# Sheet_MP3Player_DAC__V3_0.net
KiCad netlist of a schematic drawn in Altium Designer
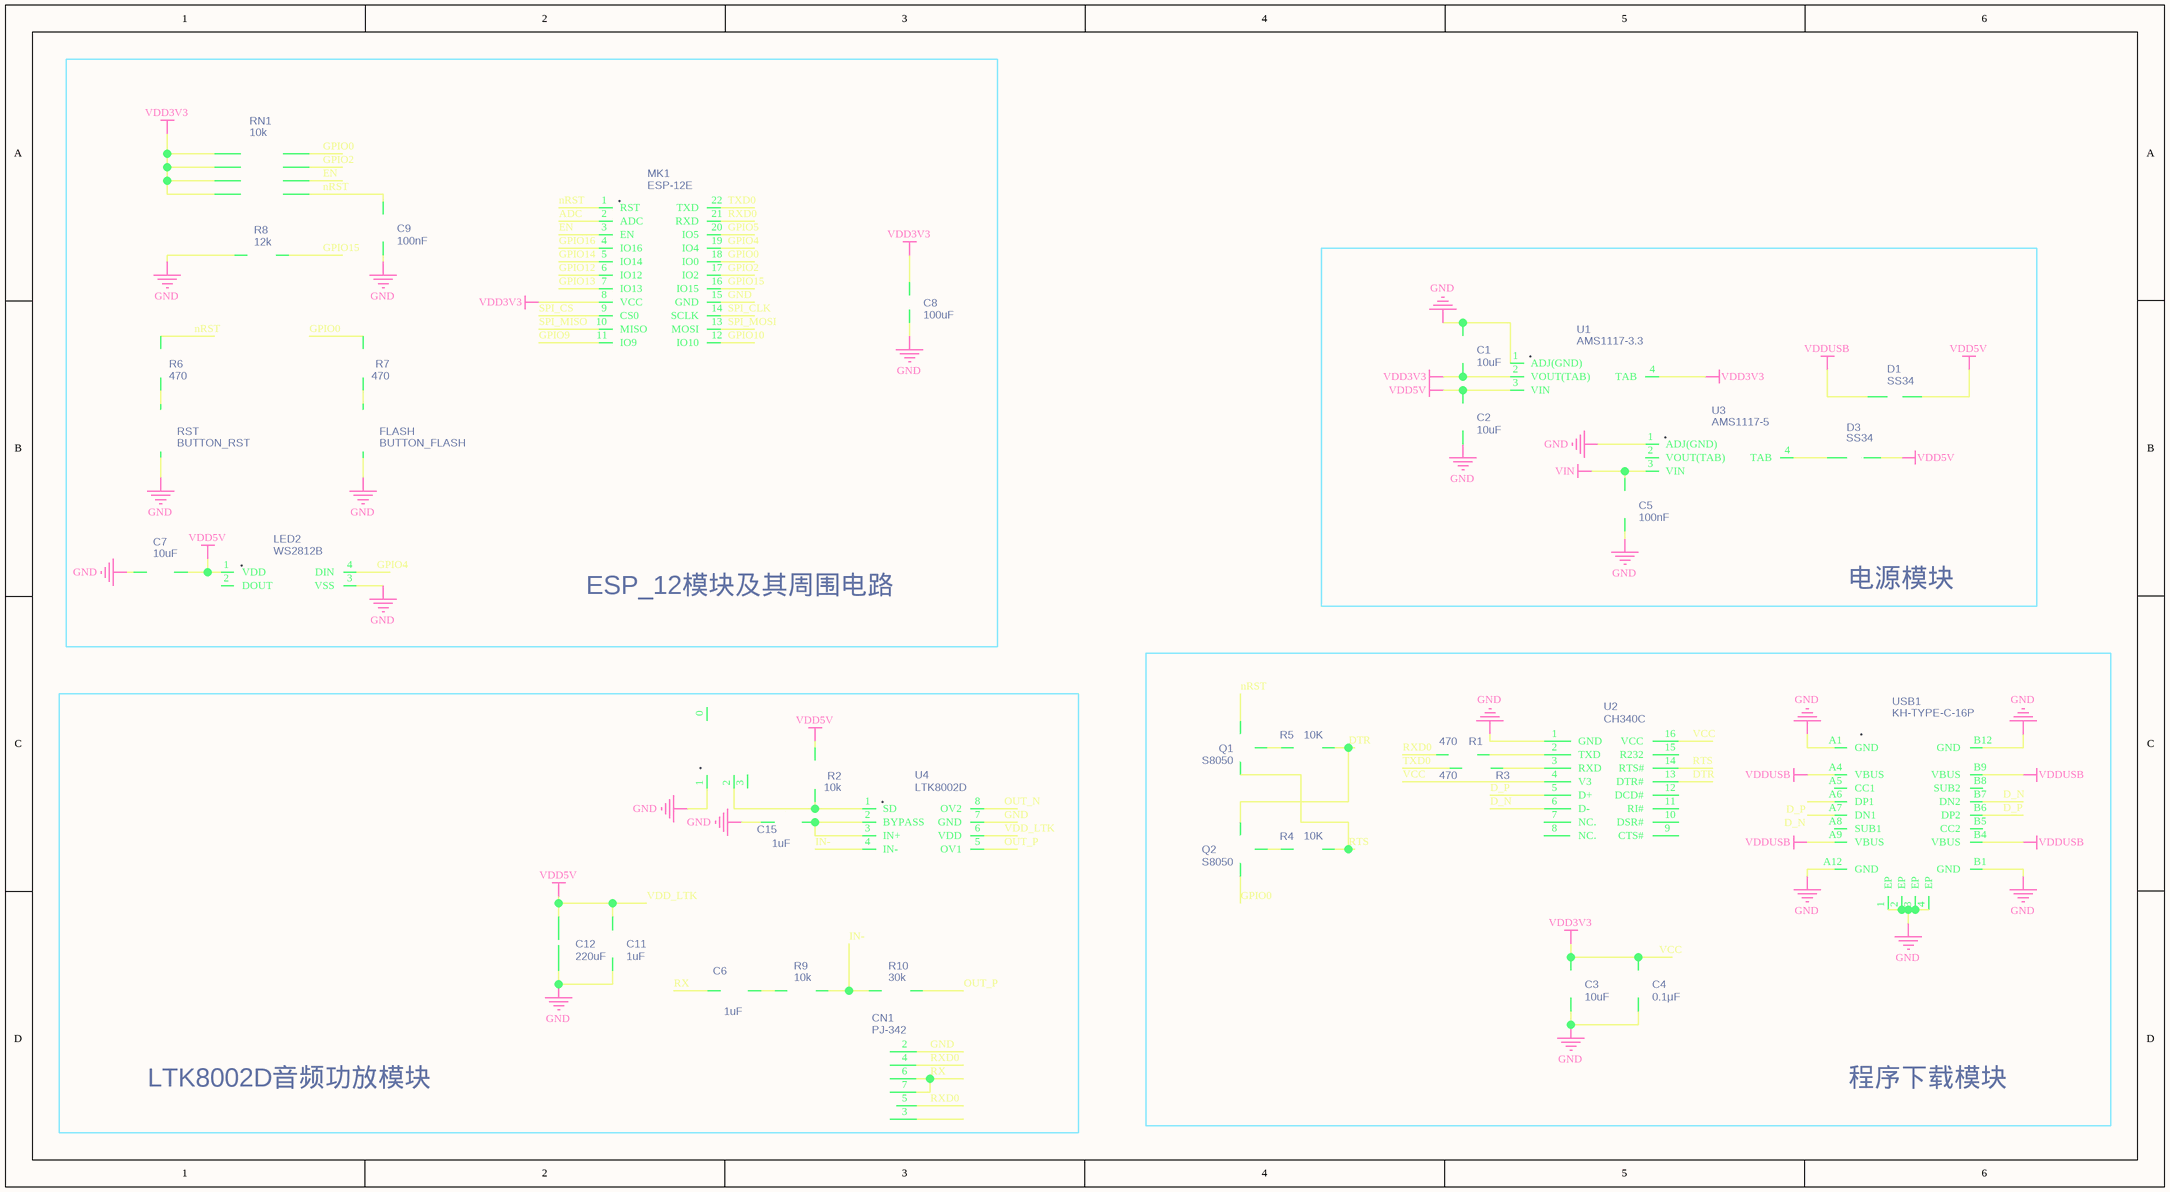
[diagram p0: Sheet_MP3Player(DAC)_V3.0.schdoc]

(export (version "E")
  (design (tool "Eeschema 10.0.6"))
  (components
    (comp (ref "C1")
      (value "10uF")
      (fields
        (field (name "BOM_SUPPLIER PART") "C338150")
        (field (name "BOM_MANUFACTURER PART") "0603B101K500CT")
        (field (name "CONTRIBUTOR") "LCSC")
      )
      (libsource (lib "altium-import") (part "root_1_10uF_"))
    )
    (comp (ref "C2")
      (value "10uF")
      (fields
        (field (name "BOM_SUPPLIER PART") "C338150")
        (field (name "BOM_MANUFACTURER PART") "0603B101K500CT")
        (field (name "CONTRIBUTOR") "LCSC")
      )
      (libsource (lib "altium-import") (part "root_1_10uF_"))
    )
    (comp (ref "C3")
      (value "10uF")
      (fields
        (field (name "BOM_SUPPLIER PART") "C338150")
        (field (name "BOM_MANUFACTURER PART") "0603B101K500CT")
        (field (name "CONTRIBUTOR") "LCSC")
      )
      (libsource (lib "altium-import") (part "root_1_10uF_"))
    )
    (comp (ref "C4")
      (value "0.1μF")
      (fields
        (field (name "BOM_SUPPLIER PART") "C338150")
        (field (name "BOM_MANUFACTURER PART") "0603B101K500CT")
        (field (name "CONTRIBUTOR") "LCSC")
      )
      (libsource (lib "altium-import") (part "root_1_0.1μF_"))
    )
    (comp (ref "C5")
      (value "100nF")
      (fields
        (field (name "BOM_SUPPLIER PART") "C338150")
        (field (name "BOM_MANUFACTURER PART") "0603B101K500CT")
        (field (name "CONTRIBUTOR") "LCSC")
      )
      (libsource (lib "altium-import") (part "root_1_100nF_"))
    )
    (comp (ref "C6")
      (value "1uF")
      (fields
        (field (name "BOM_SUPPLIER PART") "C338150")
        (field (name "BOM_MANUFACTURER PART") "0603B101K500CT")
        (field (name "CONTRIBUTOR") "LCSC")
      )
      (libsource (lib "altium-import") (part "root_0_1uF_"))
    )
    (comp (ref "C7")
      (value "10uF")
      (fields
        (field (name "BOM_SUPPLIER PART") "C338150")
        (field (name "BOM_MANUFACTURER PART") "0603B101K500CT")
        (field (name "CONTRIBUTOR") "LCSC")
      )
      (libsource (lib "altium-import") (part "root_2_10uF_"))
    )
    (comp (ref "C8")
      (value "100uF")
      (fields
        (field (name "BOM_MANUFACTURER PART") "TAJB107M006RNJ")
        (field (name "BOM_SUPPLIER PART") "C7195")
      )
      (libsource (lib "altium-import") (part "root_1_100uF_"))
    )
    (comp (ref "C9")
      (value "100nF")
      (fields
        (field (name "BOM_SUPPLIER PART") "C338150")
        (field (name "BOM_MANUFACTURER PART") "0603B101K500CT")
        (field (name "CONTRIBUTOR") "LCSC")
      )
      (libsource (lib "altium-import") (part "root_1_100nF_"))
    )
    (comp (ref "C11")
      (value "1uF")
      (fields
        (field (name "BOM_SUPPLIER PART") "C338150")
        (field (name "BOM_MANUFACTURER PART") "0603B101K500CT")
        (field (name "CONTRIBUTOR") "LCSC")
      )
      (libsource (lib "altium-import") (part "root_3_1uF_"))
    )
    (comp (ref "C12")
      (value "220uF")
      (fields
        (field (name "BOM_SUPPLIER PART") "C371974")
        (field (name "BOM_MANUFACTURER PART") "VZT221M1ETR-0607")
        (field (name "CONTRIBUTOR") "LCSC")
      )
      (libsource (lib "altium-import") (part "root_0_220uF_"))
    )
    (comp (ref "C15")
      (value "1uF")
      (fields
        (field (name "BOM_SUPPLIER PART") "C338150")
        (field (name "BOM_MANUFACTURER PART") "0603B101K500CT")
        (field (name "CONTRIBUTOR") "LCSC")
      )
      (libsource (lib "altium-import") (part "root_0_1uF_"))
    )
    (comp (ref "CN1")
      (value "PJ-342")
      (fields (field (name "BOM_SUPPLIER PART") "C668606") (field (name "CONTRIBUTOR") "LCSC"))
      (libsource (lib "altium-import") (part "root_0_PJ-342_"))
    )
    (comp (ref "D1")
      (value "SS34")
      (fields (field (name "BOM_SUPPLIER PART") "C83961"))
      (libsource (lib "") (part "root_2_SS34__1"))
    )
    (comp (ref "D3")
      (value "SS34")
      (fields (field (name "BOM_MANUFACTURER PART") "SS14") (field (name "BOM_SUPPLIER PART") "C2480"))
      (libsource (lib "altium-import") (part "root_2_SS34_"))
    )
    (comp (ref "FLASH")
      (value "BUTTON_FLASH")
      (fields (field (name "CONTRIBUTOR") "dingding1"))
      (libsource (lib "altium-import") (part "root_3_BUTTON_FLASH_"))
    )
    (comp (ref "LED2")
      (value "WS2812B")
      (fields (field (name "BOM_SUPPLIER PART") "C114585") (field (name "CONTRIBUTOR") "LCSC"))
      (libsource (lib "altium-import") (part "root_0_WS2812B_"))
    )
    (comp (ref "MK1")
      (value "ESP-12E")
      (fields (field (name "BOM_SUPPLIER PART") "C89297"))
      (libsource (lib "altium-import") (part "root_0_ESP-12E_"))
    )
    (comp (ref "OPEN1")
      (value "SK-3296S-01-L1")
      (fields (field (name "BOM_SUPPLIER PART") "C319020") (field (name "CONTRIBUTOR") "LCSC"))
      (libsource (lib "altium-import") (part "root_1_SK-3296S-01-L1_"))
    )
    (comp (ref "Q1")
      (value "S8050")
      (fields (field (name "BOM_SUPPLIER PART") "C916390") (field (name "CONTRIBUTOR") "LCSC"))
      (libsource (lib "altium-import") (part "root_0_S8050_"))
    )
    (comp (ref "Q2")
      (value "S8050")
      (fields (field (name "BOM_SUPPLIER PART") "C916390") (field (name "CONTRIBUTOR") "LCSC"))
      (libsource (lib "altium-import") (part "root_2_S8050_"))
    )
    (comp (ref "R1")
      (value "470")
      (fields
        (field (name "BOM_MANUFACTURER PART") "RC0603JR-079K1L")
        (field (name "BOM_SUPPLIER PART") "C137602")
      )
      (libsource (lib "altium-import") (part "root_2_470_"))
    )
    (comp (ref "R2")
      (value "10k")
      (fields
        (field (name "BOM_MANUFACTURER PART") "RC0603JR-079K1L")
        (field (name "BOM_SUPPLIER PART") "C137602")
      )
      (libsource (lib "") (part "root_1_10k__1"))
    )
    (comp (ref "R3")
      (value "470")
      (fields
        (field (name "BOM_MANUFACTURER PART") "RC0603JR-079K1L")
        (field (name "BOM_SUPPLIER PART") "C137602")
      )
      (libsource (lib "altium-import") (part "root_2_470_"))
    )
    (comp (ref "R4")
      (value "10K")
      (fields
        (field (name "BOM_MANUFACTURER PART") "RC0603JR-079K1L")
        (field (name "BOM_SUPPLIER PART") "C137602")
      )
      (libsource (lib "altium-import") (part "root_0_10K_"))
    )
    (comp (ref "R5")
      (value "10K")
      (fields
        (field (name "BOM_MANUFACTURER PART") "RC0603JR-079K1L")
        (field (name "BOM_SUPPLIER PART") "C137602")
      )
      (libsource (lib "altium-import") (part "root_0_10K_"))
    )
    (comp (ref "R6")
      (value "470")
      (fields
        (field (name "BOM_MANUFACTURER PART") "RC0603JR-079K1L")
        (field (name "BOM_SUPPLIER PART") "C137602")
      )
      (libsource (lib "altium-import") (part "root_1_470_"))
    )
    (comp (ref "R7")
      (value "470")
      (fields
        (field (name "BOM_MANUFACTURER PART") "RC0603JR-079K1L")
        (field (name "BOM_SUPPLIER PART") "C137602")
      )
      (libsource (lib "altium-import") (part "root_1_470_"))
    )
    (comp (ref "R8")
      (value "12k")
      (fields
        (field (name "BOM_MANUFACTURER PART") "RC0603JR-079K1L")
        (field (name "BOM_SUPPLIER PART") "C137602")
      )
      (libsource (lib "altium-import") (part "root_2_12k_"))
    )
    (comp (ref "R9")
      (value "10k")
      (fields
        (field (name "BOM_MANUFACTURER PART") "RC0603JR-079K1L")
        (field (name "BOM_SUPPLIER PART") "C137602")
      )
      (libsource (lib "altium-import") (part "root_2_10k_"))
    )
    (comp (ref "R10")
      (value "30k")
      (fields
        (field (name "BOM_MANUFACTURER PART") "RC0603JR-079K1L")
        (field (name "BOM_SUPPLIER PART") "C137602")
      )
      (libsource (lib "altium-import") (part "root_2_30k_"))
    )
    (comp (ref "RN1")
      (value "10k")
      (fields
        (field (name "BOM_MANUFACTURER PART") "YC164-FR-071KL")
        (field (name "BOM_SUPPLIER PART") "C110021")
      )
      (libsource (lib "altium-import") (part "root_1_10k_"))
    )
    (comp (ref "RST")
      (value "BUTTON_RST")
      (fields (field (name "CONTRIBUTOR") "dingding1"))
      (libsource (lib "altium-import") (part "root_3_BUTTON_RST_"))
    )
    (comp (ref "U1")
      (value "AMS1117-3.3")
      (fields (field (name "BOM_SUPPLIER PART") "C347222") (field (name "CONTRIBUTOR") "LCSC"))
      (libsource (lib "altium-import") (part "root_0_AMS1117-3.3_"))
    )
    (comp (ref "U2")
      (value "CH340C")
      (fields (field (name "BOM_SUPPLIER PART") "C84681"))
      (libsource (lib "altium-import") (part "root_0_CH340C_"))
    )
    (comp (ref "U3")
      (value "AMS1117-5")
      (fields
        (field (name "BOM_SUPPLIER PART") "C347222")
        (field (name "BOM_MANUFACTURER PART") "AMS1117-3.3")
        (field (name "CONTRIBUTOR") "LCSC")
      )
      (libsource (lib "altium-import") (part "root_0_AMS1117-5_"))
    )
    (comp (ref "U4")
      (value "LTK8002D")
      (fields (field (name "BOM_SUPPLIER PART") "C406248") (field (name "CONTRIBUTOR") "LCSC"))
      (libsource (lib "altium-import") (part "root_0_LTK8002D_"))
    )
    (comp (ref "USB1")
      (value "KH-TYPE-C-16P")
      (fields (field (name "BOM_SUPPLIER PART") "C709357") (field (name "CONTRIBUTOR") "LCSC"))
      (libsource (lib "altium-import") (part "root_0_KH-TYPE-C-16P_"))
    )
  )
  (nets
    (net (code "1") (name "/ADC") (class "Default")
      (node (ref "MK1") (pin "2") (pinfunction "ADC_2") (pintype "passive"))
    )
    (net (code "2") (name "/DTR") (class "Default")
      (node (ref "Q2") (pin "2") (pinfunction "E_2") (pintype "passive"))
      (node (ref "R5") (pin "2") (pinfunction "2_2") (pintype "passive"))
      (node (ref "U2") (pin "13") (pinfunction "DTR#_13") (pintype "passive"))
    )
    (net (code "3") (name "/D_N") (class "Default")
      (node (ref "U2") (pin "6") (pinfunction "D-_6") (pintype "passive"))
      (node (ref "USB1") (pin "A7") (pinfunction "DN1_A7") (pintype "passive"))
      (node (ref "USB1") (pin "B7") (pinfunction "DN2_B7") (pintype "passive"))
    )
    (net (code "4") (name "/D_P") (class "Default")
      (node (ref "U2") (pin "5") (pinfunction "D+_5") (pintype "passive"))
      (node (ref "USB1") (pin "A6") (pinfunction "DP1_A6") (pintype "passive"))
      (node (ref "USB1") (pin "B6") (pinfunction "DP2_B6") (pintype "passive"))
    )
    (net (code "5") (name "/EN") (class "Default")
      (node (ref "MK1") (pin "3") (pinfunction "EN_3") (pintype "passive"))
      (node (ref "RN1") (pin "2") (pinfunction "2_2") (pintype "passive"))
    )
    (net (code "6") (name "/GPIO0") (class "Default")
      (node (ref "MK1") (pin "18") (pinfunction "IO0_18") (pintype "passive"))
      (node (ref "Q2") (pin "3") (pinfunction "C_3") (pintype "passive"))
      (node (ref "R7") (pin "2") (pinfunction "2_2") (pintype "passive"))
      (node (ref "RN1") (pin "4") (pinfunction "4_4") (pintype "passive"))
    )
    (net (code "7") (name "/GPIO2") (class "Default")
      (node (ref "MK1") (pin "17") (pinfunction "IO2_17") (pintype "passive"))
      (node (ref "RN1") (pin "3") (pinfunction "3_3") (pintype "passive"))
    )
    (net (code "8") (name "/GPIO4") (class "Default")
      (node (ref "LED2") (pin "4") (pinfunction "DIN_4") (pintype "passive"))
      (node (ref "MK1") (pin "19") (pinfunction "IO4_19") (pintype "passive"))
    )
    (net (code "9") (name "/GPIO5") (class "Default")
      (node (ref "MK1") (pin "20") (pinfunction "IO5_20") (pintype "passive"))
    )
    (net (code "10") (name "/GPIO9") (class "Default")
      (node (ref "MK1") (pin "11") (pinfunction "IO9_11") (pintype "passive"))
    )
    (net (code "11") (name "/GPIO10") (class "Default")
      (node (ref "MK1") (pin "12") (pinfunction "IO10_12") (pintype "passive"))
    )
    (net (code "12") (name "/GPIO12") (class "Default")
      (node (ref "MK1") (pin "6") (pinfunction "IO12_6") (pintype "passive"))
    )
    (net (code "13") (name "/GPIO13") (class "Default")
      (node (ref "MK1") (pin "7") (pinfunction "IO13_7") (pintype "passive"))
    )
    (net (code "14") (name "/GPIO14") (class "Default")
      (node (ref "MK1") (pin "5") (pinfunction "IO14_5") (pintype "passive"))
    )
    (net (code "15") (name "/GPIO15") (class "Default")
      (node (ref "MK1") (pin "16") (pinfunction "IO15_16") (pintype "passive"))
      (node (ref "R8") (pin "1") (pinfunction "1_1") (pintype "passive"))
    )
    (net (code "16") (name "/GPIO16") (class "Default")
      (node (ref "MK1") (pin "4") (pinfunction "IO16_4") (pintype "passive"))
    )
    (net (code "17") (name "/IN-") (class "Default")
      (node (ref "R10") (pin "2") (pinfunction "2_2") (pintype "passive"))
      (node (ref "R9") (pin "1") (pinfunction "1_1") (pintype "passive"))
      (node (ref "U4") (pin "4") (pinfunction "IN-_4") (pintype "passive"))
    )
    (net (code "18") (name "/OUT_N") (class "Default")
      (node (ref "U4") (pin "8") (pinfunction "OV2_8") (pintype "passive"))
    )
    (net (code "19") (name "/OUT_P") (class "Default")
      (node (ref "R10") (pin "1") (pinfunction "1_1") (pintype "passive"))
      (node (ref "U4") (pin "5") (pinfunction "OV1_5") (pintype "passive"))
    )
    (net (code "20") (name "/RTS") (class "Default")
      (node (ref "Q1") (pin "2") (pinfunction "E_2") (pintype "passive"))
      (node (ref "R4") (pin "2") (pinfunction "2_2") (pintype "passive"))
      (node (ref "U2") (pin "14") (pinfunction "RTS#_14") (pintype "passive"))
    )
    (net (code "21") (name "/RX") (class "Default")
      (node (ref "C6") (pin "2") (pinfunction "2_2") (pintype "passive"))
      (node (ref "CN1") (pin "6") (pinfunction "6_6") (pintype "passive"))
      (node (ref "CN1") (pin "7") (pinfunction "7_7") (pintype "passive"))
    )
    (net (code "22") (name "/RXD0") (class "Default")
      (node (ref "CN1") (pin "4") (pinfunction "4_4") (pintype "passive"))
      (node (ref "CN1") (pin "5") (pinfunction "5_5") (pintype "passive"))
      (node (ref "MK1") (pin "21") (pinfunction "RXD_21") (pintype "passive"))
      (node (ref "R1") (pin "2") (pinfunction "2_2") (pintype "passive"))
    )
    (net (code "23") (name "/SPI_CLK") (class "Default")
      (node (ref "MK1") (pin "14") (pinfunction "SCLK_14") (pintype "passive"))
    )
    (net (code "24") (name "/SPI_CS") (class "Default")
      (node (ref "MK1") (pin "9") (pinfunction "CS0_9") (pintype "passive"))
    )
    (net (code "25") (name "/SPI_MISO") (class "Default")
      (node (ref "MK1") (pin "10") (pinfunction "MISO_10") (pintype "passive"))
    )
    (net (code "26") (name "/SPI_MOSI") (class "Default")
      (node (ref "MK1") (pin "13") (pinfunction "MOSI_13") (pintype "passive"))
    )
    (net (code "27") (name "/TXD0") (class "Default")
      (node (ref "MK1") (pin "22") (pinfunction "TXD_22") (pintype "passive"))
      (node (ref "R3") (pin "2") (pinfunction "2_2") (pintype "passive"))
    )
    (net (code "28") (name "/nRST") (class "Default")
      (node (ref "C9") (pin "1") (pinfunction "1_1") (pintype "passive"))
      (node (ref "MK1") (pin "1") (pinfunction "RST_1") (pintype "passive"))
      (node (ref "Q1") (pin "3") (pinfunction "C_3") (pintype "passive"))
      (node (ref "R6") (pin "2") (pinfunction "2_2") (pintype "passive"))
      (node (ref "RN1") (pin "1") (pinfunction "1_1") (pintype "passive"))
    )
    (net (code "29") (name "GND") (class "Default")
      (node (ref "C1") (pin "1") (pinfunction "1_1") (pintype "passive"))
      (node (ref "C11") (pin "1") (pinfunction "1_1") (pintype "passive"))
      (node (ref "C12") (pin "2") (pinfunction "2_2") (pintype "passive"))
      (node (ref "C15") (pin "2") (pinfunction "2_2") (pintype "passive"))
      (node (ref "C2") (pin "2") (pinfunction "2_2") (pintype "passive"))
      (node (ref "C3") (pin "2") (pinfunction "2_2") (pintype "passive"))
      (node (ref "C4") (pin "2") (pinfunction "2_2") (pintype "passive"))
      (node (ref "C5") (pin "2") (pinfunction "2_2") (pintype "passive"))
      (node (ref "C7") (pin "1") (pinfunction "1_1") (pintype "passive"))
      (node (ref "C8") (pin "2") (pinfunction "2_2") (pintype "passive"))
      (node (ref "C9") (pin "2") (pinfunction "2_2") (pintype "passive"))
      (node (ref "CN1") (pin "2") (pinfunction "2_2") (pintype "passive"))
      (node (ref "FLASH") (pin "2") (pinfunction "2_2") (pintype "passive"))
      (node (ref "LED2") (pin "3") (pinfunction "VSS_3") (pintype "passive"))
      (node (ref "MK1") (pin "15") (pinfunction "GND_15") (pintype "passive"))
      (node (ref "OPEN1") (pin "1") (pinfunction "1_1") (pintype "passive"))
      (node (ref "R8") (pin "2") (pinfunction "2_2") (pintype "passive"))
      (node (ref "RST") (pin "2") (pinfunction "2_2") (pintype "passive"))
      (node (ref "U1") (pin "1") (pinfunction "ADJ(GND)_1") (pintype "passive"))
      (node (ref "U2") (pin "1") (pinfunction "GND_1") (pintype "passive"))
      (node (ref "U3") (pin "1") (pinfunction "ADJ(GND)_1") (pintype "passive"))
      (node (ref "U4") (pin "7") (pinfunction "GND_7") (pintype "passive"))
      (node (ref "USB1") (pin "1") (pinfunction "EP_1") (pintype "passive"))
      (node (ref "USB1") (pin "2") (pinfunction "EP_2") (pintype "passive"))
      (node (ref "USB1") (pin "3") (pinfunction "EP_3") (pintype "passive"))
      (node (ref "USB1") (pin "4") (pinfunction "EP_4") (pintype "passive"))
      (node (ref "USB1") (pin "A1") (pinfunction "GND_A1") (pintype "passive"))
      (node (ref "USB1") (pin "A12") (pinfunction "GND_A12") (pintype "passive"))
      (node (ref "USB1") (pin "B1") (pinfunction "GND_B1") (pintype "passive"))
      (node (ref "USB1") (pin "B12") (pinfunction "GND_B12") (pintype "passive"))
    )
    (net (code "30") (name "Net-(C6-Pad1)") (class "Default")
      (node (ref "C6") (pin "1") (pinfunction "1_1") (pintype "passive"))
      (node (ref "R9") (pin "2") (pinfunction "2_2") (pintype "passive"))
    )
    (net (code "31") (name "Net-(D3-A)") (class "Default")
      (node (ref "D3") (pin "2") (pinfunction "A_2") (pintype "passive"))
      (node (ref "U3") (pin "4") (pinfunction "TAB_4") (pintype "passive"))
    )
    (net (code "32") (name "Net-(FLASH-Pad1)") (class "Default")
      (node (ref "FLASH") (pin "1") (pinfunction "1_1") (pintype "passive"))
      (node (ref "R7") (pin "1") (pinfunction "1_1") (pintype "passive"))
    )
    (net (code "33") (name "Net-(Q1-B)") (class "Default")
      (node (ref "Q1") (pin "1") (pinfunction "B_1") (pintype "passive"))
      (node (ref "R5") (pin "1") (pinfunction "1_1") (pintype "passive"))
    )
    (net (code "34") (name "Net-(Q2-B)") (class "Default")
      (node (ref "Q2") (pin "1") (pinfunction "B_1") (pintype "passive"))
      (node (ref "R4") (pin "1") (pinfunction "1_1") (pintype "passive"))
    )
    (net (code "35") (name "Net-(R6-Pad1)") (class "Default")
      (node (ref "R6") (pin "1") (pinfunction "1_1") (pintype "passive"))
      (node (ref "RST") (pin "1") (pinfunction "1_1") (pintype "passive"))
    )
    (net (code "36") (name "Net-(U2-RXD)") (class "Default")
      (node (ref "R3") (pin "1") (pinfunction "1_1") (pintype "passive"))
      (node (ref "U2") (pin "3") (pinfunction "RXD_3") (pintype "passive"))
    )
    (net (code "37") (name "Net-(U2-TXD)") (class "Default")
      (node (ref "R1") (pin "1") (pinfunction "1_1") (pintype "passive"))
      (node (ref "U2") (pin "2") (pinfunction "TXD_2") (pintype "passive"))
    )
    (net (code "38") (name "Net-(U4-BYPASS)") (class "Default")
      (node (ref "C15") (pin "1") (pinfunction "1_1") (pintype "passive"))
      (node (ref "U4") (pin "2") (pinfunction "BYPASS_2") (pintype "passive"))
      (node (ref "U4") (pin "3") (pinfunction "IN+_3") (pintype "passive"))
    )
    (net (code "39") (name "Net-(U4-SD)") (class "Default")
      (node (ref "OPEN1") (pin "2") (pinfunction "2_2") (pintype "passive"))
      (node (ref "R2") (pin "1") (pinfunction "1_1") (pintype "passive"))
      (node (ref "U4") (pin "1") (pinfunction "SD_1") (pintype "passive"))
    )
    (net (code "40") (name "VDD3V3") (class "Default")
      (node (ref "C1") (pin "2") (pinfunction "2_2") (pintype "passive"))
      (node (ref "C3") (pin "1") (pinfunction "1_1") (pintype "passive"))
      (node (ref "C4") (pin "1") (pinfunction "1_1") (pintype "passive"))
      (node (ref "C8") (pin "1") (pinfunction "1_1") (pintype "passive"))
      (node (ref "MK1") (pin "8") (pinfunction "VCC_8") (pintype "passive"))
      (node (ref "RN1") (pin "5") (pinfunction "5_5") (pintype "passive"))
      (node (ref "RN1") (pin "6") (pinfunction "6_6") (pintype "passive"))
      (node (ref "RN1") (pin "7") (pinfunction "7_7") (pintype "passive"))
      (node (ref "RN1") (pin "8") (pinfunction "8_8") (pintype "passive"))
      (node (ref "U1") (pin "2") (pinfunction "VOUT(TAB)_2") (pintype "passive"))
      (node (ref "U1") (pin "4") (pinfunction "TAB_4") (pintype "passive"))
      (node (ref "U2") (pin "16") (pinfunction "VCC_16") (pintype "passive"))
      (node (ref "U2") (pin "4") (pinfunction "V3_4") (pintype "passive"))
    )
    (net (code "41") (name "VDD5V") (class "Default")
      (node (ref "C11") (pin "2") (pinfunction "2_2") (pintype "passive"))
      (node (ref "C12") (pin "1") (pinfunction "1_1") (pintype "passive"))
      (node (ref "C2") (pin "1") (pinfunction "1_1") (pintype "passive"))
      (node (ref "C7") (pin "2") (pinfunction "2_2") (pintype "passive"))
      (node (ref "D1") (pin "1") (pinfunction "C_1") (pintype "passive"))
      (node (ref "D3") (pin "1") (pinfunction "K_1") (pintype "passive"))
      (node (ref "LED2") (pin "1") (pinfunction "VDD_1") (pintype "passive"))
      (node (ref "R2") (pin "2") (pinfunction "2_2") (pintype "passive"))
      (node (ref "U1") (pin "3") (pinfunction "VIN_3") (pintype "passive"))
      (node (ref "U4") (pin "6") (pinfunction "VDD_6") (pintype "passive"))
    )
    (net (code "42") (name "VDDUSB") (class "Default")
      (node (ref "D1") (pin "2") (pinfunction "A_2") (pintype "passive"))
      (node (ref "USB1") (pin "A4") (pinfunction "VBUS_A4") (pintype "passive"))
      (node (ref "USB1") (pin "A9") (pinfunction "VBUS_A9") (pintype "passive"))
      (node (ref "USB1") (pin "B4") (pinfunction "VBUS_B4") (pintype "passive"))
      (node (ref "USB1") (pin "B9") (pinfunction "VBUS_B9") (pintype "passive"))
    )
    (net (code "43") (name "VIN") (class "Default")
      (node (ref "C5") (pin "1") (pinfunction "1_1") (pintype "passive"))
      (node (ref "U3") (pin "3") (pinfunction "VIN_3") (pintype "passive"))
    )
    (net (code "44") (name "unconnected-(CN1-Pad3)") (class "Default")
      (node (ref "CN1") (pin "3") (pinfunction "3_3") (pintype "passive"))
    )
    (net (code "45") (name "unconnected-(LED2-DOUT-Pad2)") (class "Default")
      (node (ref "LED2") (pin "2") (pinfunction "DOUT_2") (pintype "passive"))
    )
    (net (code "46") (name "unconnected-(OPEN1-Pad0)") (class "Default")
      (node (ref "OPEN1") (pin "0") (pinfunction "0_0") (pintype "passive"))
    )
    (net (code "47") (name "unconnected-(OPEN1-Pad3)") (class "Default")
      (node (ref "OPEN1") (pin "3") (pinfunction "3_3") (pintype "passive"))
    )
    (net (code "48") (name "unconnected-(U2-CTS#-Pad9)") (class "Default")
      (node (ref "U2") (pin "9") (pinfunction "CTS#_9") (pintype "passive"))
    )
    (net (code "49") (name "unconnected-(U2-DCD#-Pad12)") (class "Default")
      (node (ref "U2") (pin "12") (pinfunction "DCD#_12") (pintype "passive"))
    )
    (net (code "50") (name "unconnected-(U2-DSR#-Pad10)") (class "Default")
      (node (ref "U2") (pin "10") (pinfunction "DSR#_10") (pintype "passive"))
    )
    (net (code "51") (name "unconnected-(U2-NC.-Pad7)") (class "Default")
      (node (ref "U2") (pin "7") (pinfunction "NC._7") (pintype "passive"))
    )
    (net (code "52") (name "unconnected-(U2-NC.-Pad8)") (class "Default")
      (node (ref "U2") (pin "8") (pinfunction "NC._8") (pintype "passive"))
    )
    (net (code "53") (name "unconnected-(U2-R232-Pad15)") (class "Default")
      (node (ref "U2") (pin "15") (pinfunction "R232_15") (pintype "passive"))
    )
    (net (code "54") (name "unconnected-(U2-RI#-Pad11)") (class "Default")
      (node (ref "U2") (pin "11") (pinfunction "RI#_11") (pintype "passive"))
    )
    (net (code "55") (name "unconnected-(U3-VOUT(TAB)-Pad2)") (class "Default")
      (node (ref "U3") (pin "2") (pinfunction "VOUT(TAB)_2") (pintype "passive"))
    )
    (net (code "56") (name "unconnected-(USB1-CC1-PadA5)") (class "Default")
      (node (ref "USB1") (pin "A5") (pinfunction "CC1_A5") (pintype "passive"))
    )
    (net (code "57") (name "unconnected-(USB1-CC2-PadB5)") (class "Default")
      (node (ref "USB1") (pin "B5") (pinfunction "CC2_B5") (pintype "passive"))
    )
    (net (code "58") (name "unconnected-(USB1-SUB1-PadA8)") (class "Default")
      (node (ref "USB1") (pin "A8") (pinfunction "SUB1_A8") (pintype "passive"))
    )
    (net (code "59") (name "unconnected-(USB1-SUB2-PadB8)") (class "Default")
      (node (ref "USB1") (pin "B8") (pinfunction "SUB2_B8") (pintype "passive"))
    )
  )
)
